# 12_GPS_MIPI_EIM.net
KiCad netlist of a schematic drawn in Altium Designer
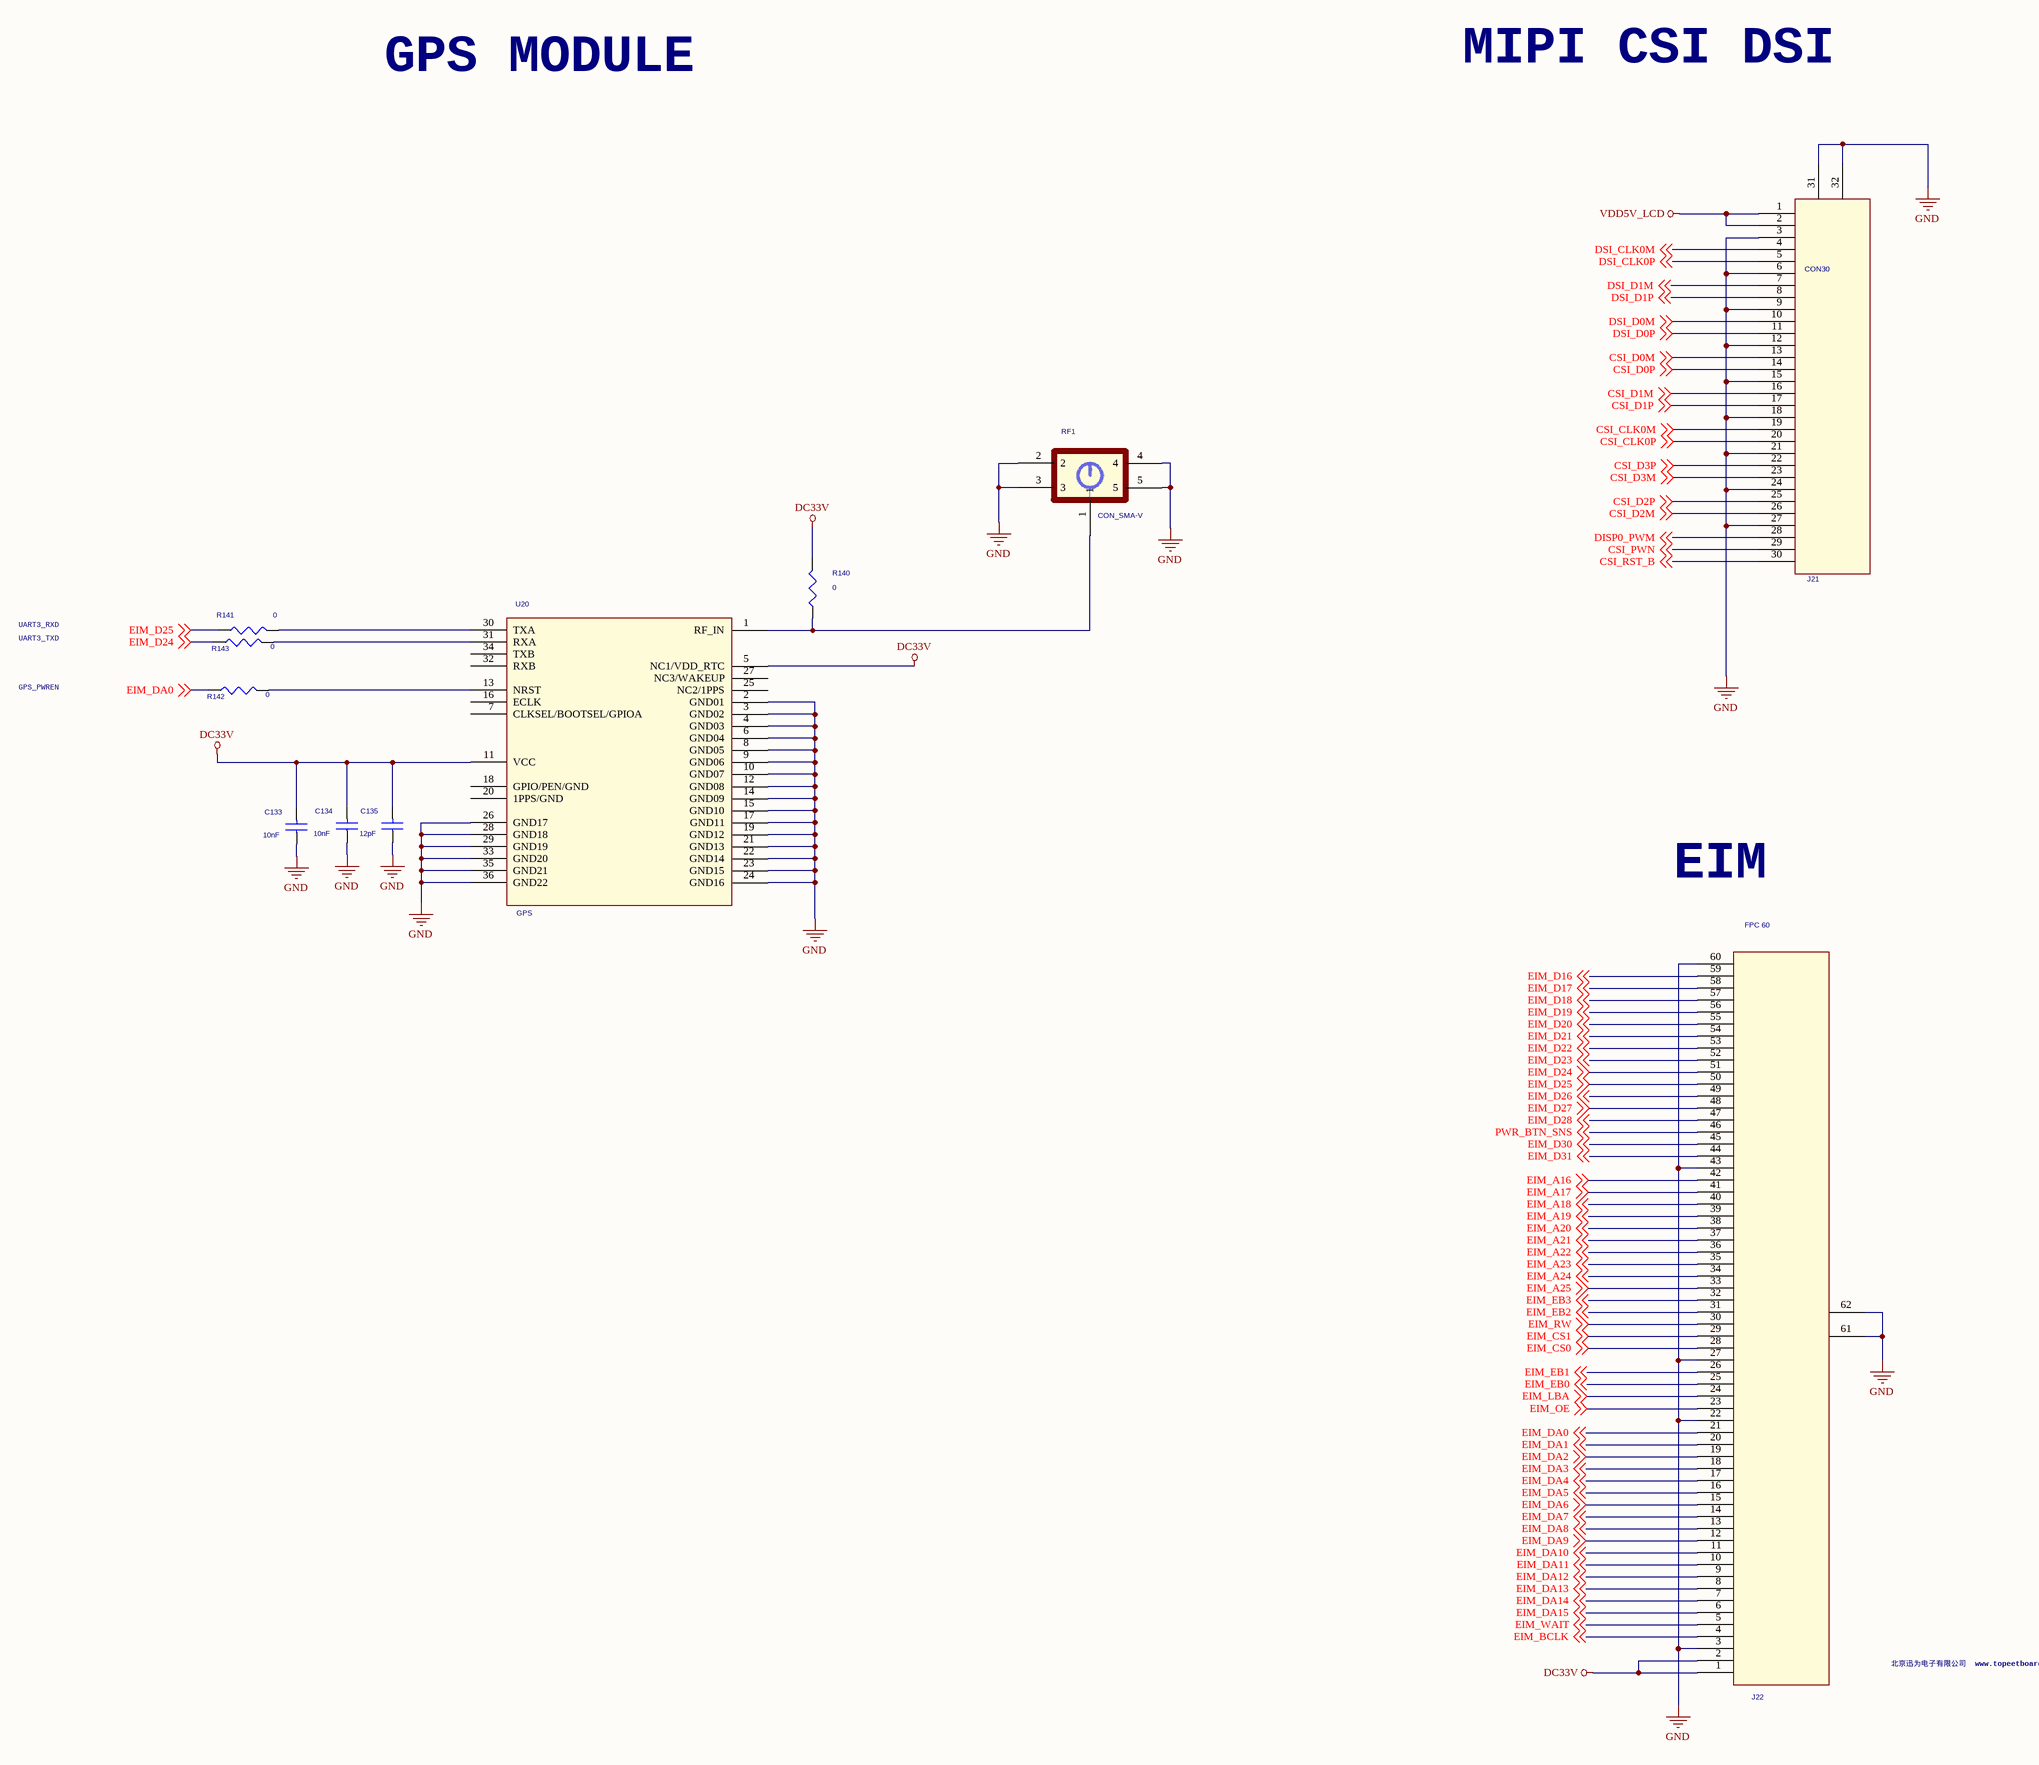
[diagram p0: 12 GPS,MIPI,EIM.SchDoc]

(export (version "E")
  (design (tool "Eeschema 10.0.6"))
  (components
    (comp (ref "C133") (value "10nF") (footprint "C1005") (libsource (lib "*") (part "C1005_Dup1")))
    (comp (ref "C134") (value "10nF") (footprint "C1005") (libsource (lib "*") (part "C1005_Dup1")))
    (comp (ref "C135") (value "12pF") (footprint "C1005") (libsource (lib "*") (part "C1005_Dup1")))
    (comp (ref "J21") (value "CON30") (libsource (lib "*") (part "LVDS_QM_2")))
    (comp (ref "J22") (value "FPC 60") (libsource (lib "*") (part "HEADER 60_1")))
    (comp (ref "R140") (value "0") (footprint "R1005") (libsource (lib "*") (part "R1005_0_Dup1")))
    (comp (ref "R141") (value "0") (footprint "R1005") (libsource (lib "*") (part "R1005_0_Dup1")))
    (comp (ref "R142") (value "0") (footprint "R1005") (libsource (lib "*") (part "R1005_0_Dup1")))
    (comp (ref "R143") (value "0") (footprint "R1005") (libsource (lib "*") (part "R1005_0_Dup1")))
    (comp (ref "RF1") (value "CON_SMA-V") (libsource (lib "*") (part "CON_SMA-V")))
    (comp (ref "U20") (value "GPS") (libsource (lib "*") (part "SM-05")))
  )
  (nets
    (net (code "1") (name "CSI_CLK0M") (class "Default")
      (node (ref "J21") (pin "19") (pinfunction "$PIN11_19") (pintype "passive"))
    )
    (net (code "2") (name "CSI_CLK0P") (class "Default")
      (node (ref "J21") (pin "20") (pinfunction "$PIN10_20") (pintype "passive"))
    )
    (net (code "3") (name "CSI_D0M") (class "Default")
      (node (ref "J21") (pin "13") (pinfunction "$PIN17_13") (pintype "passive"))
    )
    (net (code "4") (name "CSI_D0P") (class "Default")
      (node (ref "J21") (pin "14") (pinfunction "$PIN16_14") (pintype "passive"))
    )
    (net (code "5") (name "CSI_D1M") (class "Default")
      (node (ref "J21") (pin "16") (pinfunction "$PIN14_16") (pintype "passive"))
    )
    (net (code "6") (name "CSI_D1P") (class "Default")
      (node (ref "J21") (pin "17") (pinfunction "$PIN13_17") (pintype "passive"))
    )
    (net (code "7") (name "CSI_D2M") (class "Default")
      (node (ref "J21") (pin "26") (pinfunction "$PIN4_26") (pintype "passive"))
    )
    (net (code "8") (name "CSI_D2P") (class "Default")
      (node (ref "J21") (pin "25") (pinfunction "$PIN5_25") (pintype "passive"))
    )
    (net (code "9") (name "CSI_D3M") (class "Default")
      (node (ref "J21") (pin "23") (pinfunction "$PIN7_23") (pintype "passive"))
    )
    (net (code "10") (name "CSI_D3P") (class "Default")
      (node (ref "J21") (pin "22") (pinfunction "$PIN8_22") (pintype "passive"))
    )
    (net (code "11") (name "CSI_PWN") (class "Default")
      (node (ref "J21") (pin "29") (pinfunction "$PIN1_29") (pintype "passive"))
    )
    (net (code "12") (name "CSI_RST_B") (class "Default")
      (node (ref "J21") (pin "30") (pinfunction "$PIN0_30") (pintype "passive"))
    )
    (net (code "13") (name "DC33V") (class "Default")
      (node (ref "C133") (pin "2") (pinfunction "2_2") (pintype "passive"))
      (node (ref "C134") (pin "2") (pinfunction "2_2") (pintype "passive"))
      (node (ref "C135") (pin "2") (pinfunction "2_2") (pintype "passive"))
      (node (ref "J22") (pin "1") (pinfunction "1_1") (pintype "passive"))
      (node (ref "J22") (pin "2") (pinfunction "2_2") (pintype "passive"))
      (node (ref "R140") (pin "2") (pinfunction "2_2") (pintype "passive"))
      (node (ref "U20") (pin "11") (pinfunction "VCC_11") (pintype "passive"))
      (node (ref "U20") (pin "5") (pinfunction "NC1/VDD_RTC_5") (pintype "passive"))
    )
    (net (code "14") (name "DISP0_PWM") (class "Default")
      (node (ref "J21") (pin "28") (pinfunction "$PIN2_28") (pintype "passive"))
    )
    (net (code "15") (name "DSI_CLK0M") (class "Default")
      (node (ref "J21") (pin "4") (pinfunction "$PIN27_4") (pintype "passive"))
    )
    (net (code "16") (name "DSI_CLK0P") (class "Default")
      (node (ref "J21") (pin "5") (pinfunction "$PIN26_5") (pintype "passive"))
    )
    (net (code "17") (name "DSI_D0M") (class "Default")
      (node (ref "J21") (pin "10") (pinfunction "$PIN20_10") (pintype "passive"))
    )
    (net (code "18") (name "DSI_D0P") (class "Default")
      (node (ref "J21") (pin "11") (pinfunction "$PIN19_11") (pintype "passive"))
    )
    (net (code "19") (name "DSI_D1M") (class "Default")
      (node (ref "J21") (pin "7") (pinfunction "$PIN24_7") (pintype "passive"))
    )
    (net (code "20") (name "DSI_D1P") (class "Default")
      (node (ref "J21") (pin "8") (pinfunction "$PIN22_8") (pintype "passive"))
    )
    (net (code "21") (name "EIM_A16") (class "Default")
      (node (ref "J22") (pin "42") (pinfunction "42_42") (pintype "passive"))
    )
    (net (code "22") (name "EIM_A17") (class "Default")
      (node (ref "J22") (pin "41") (pinfunction "41_41") (pintype "passive"))
    )
    (net (code "23") (name "EIM_A18") (class "Default")
      (node (ref "J22") (pin "40") (pinfunction "40_40") (pintype "passive"))
    )
    (net (code "24") (name "EIM_A19") (class "Default")
      (node (ref "J22") (pin "39") (pinfunction "39_39") (pintype "passive"))
    )
    (net (code "25") (name "EIM_A20") (class "Default")
      (node (ref "J22") (pin "38") (pinfunction "38_38") (pintype "passive"))
    )
    (net (code "26") (name "EIM_A21") (class "Default")
      (node (ref "J22") (pin "37") (pinfunction "37_37") (pintype "passive"))
    )
    (net (code "27") (name "EIM_A22") (class "Default")
      (node (ref "J22") (pin "36") (pinfunction "36_36") (pintype "passive"))
    )
    (net (code "28") (name "EIM_A23") (class "Default")
      (node (ref "J22") (pin "35") (pinfunction "35_35") (pintype "passive"))
    )
    (net (code "29") (name "EIM_A24") (class "Default")
      (node (ref "J22") (pin "34") (pinfunction "34_34") (pintype "passive"))
    )
    (net (code "30") (name "EIM_A25") (class "Default")
      (node (ref "J22") (pin "33") (pinfunction "33_33") (pintype "passive"))
    )
    (net (code "31") (name "EIM_BCLK") (class "Default")
      (node (ref "J22") (pin "4") (pinfunction "4_4") (pintype "passive"))
    )
    (net (code "32") (name "EIM_CS0") (class "Default")
      (node (ref "J22") (pin "28") (pinfunction "28_28") (pintype "passive"))
    )
    (net (code "33") (name "EIM_CS1") (class "Default")
      (node (ref "J22") (pin "29") (pinfunction "29_29") (pintype "passive"))
    )
    (net (code "34") (name "EIM_D16") (class "Default")
      (node (ref "J22") (pin "59") (pinfunction "59_59") (pintype "passive"))
    )
    (net (code "35") (name "EIM_D17") (class "Default")
      (node (ref "J22") (pin "58") (pinfunction "58_58") (pintype "passive"))
    )
    (net (code "36") (name "EIM_D18") (class "Default")
      (node (ref "J22") (pin "57") (pinfunction "57_57") (pintype "passive"))
    )
    (net (code "37") (name "EIM_D19") (class "Default")
      (node (ref "J22") (pin "56") (pinfunction "56_56") (pintype "passive"))
    )
    (net (code "38") (name "EIM_D20") (class "Default")
      (node (ref "J22") (pin "55") (pinfunction "55_55") (pintype "passive"))
    )
    (net (code "39") (name "EIM_D21") (class "Default")
      (node (ref "J22") (pin "54") (pinfunction "54_54") (pintype "passive"))
    )
    (net (code "40") (name "EIM_D22") (class "Default")
      (node (ref "J22") (pin "53") (pinfunction "53_53") (pintype "passive"))
    )
    (net (code "41") (name "EIM_D23") (class "Default")
      (node (ref "J22") (pin "52") (pinfunction "52_52") (pintype "passive"))
    )
    (net (code "42") (name "EIM_D24") (class "Default")
      (node (ref "J22") (pin "51") (pinfunction "51_51") (pintype "passive"))
      (node (ref "R143") (pin "1") (pinfunction "1_1") (pintype "passive"))
    )
    (net (code "43") (name "EIM_D25") (class "Default")
      (node (ref "J22") (pin "50") (pinfunction "50_50") (pintype "passive"))
      (node (ref "R141") (pin "1") (pinfunction "1_1") (pintype "passive"))
    )
    (net (code "44") (name "EIM_D26") (class "Default")
      (node (ref "J22") (pin "49") (pinfunction "49_49") (pintype "passive"))
    )
    (net (code "45") (name "EIM_D27") (class "Default")
      (node (ref "J22") (pin "48") (pinfunction "48_48") (pintype "passive"))
    )
    (net (code "46") (name "EIM_D28") (class "Default")
      (node (ref "J22") (pin "47") (pinfunction "47_47") (pintype "passive"))
    )
    (net (code "47") (name "EIM_D30") (class "Default")
      (node (ref "J22") (pin "45") (pinfunction "45_45") (pintype "passive"))
    )
    (net (code "48") (name "EIM_D31") (class "Default")
      (node (ref "J22") (pin "44") (pinfunction "44_44") (pintype "passive"))
    )
    (net (code "49") (name "EIM_DA0") (class "Default")
      (node (ref "J22") (pin "21") (pinfunction "21_21") (pintype "passive"))
      (node (ref "R142") (pin "1") (pinfunction "1_1") (pintype "passive"))
    )
    (net (code "50") (name "EIM_DA1") (class "Default")
      (node (ref "J22") (pin "20") (pinfunction "20_20") (pintype "passive"))
    )
    (net (code "51") (name "EIM_DA2") (class "Default")
      (node (ref "J22") (pin "19") (pinfunction "19_19") (pintype "passive"))
    )
    (net (code "52") (name "EIM_DA3") (class "Default")
      (node (ref "J22") (pin "18") (pinfunction "18_18") (pintype "passive"))
    )
    (net (code "53") (name "EIM_DA4") (class "Default")
      (node (ref "J22") (pin "17") (pinfunction "17_17") (pintype "passive"))
    )
    (net (code "54") (name "EIM_DA5") (class "Default")
      (node (ref "J22") (pin "16") (pinfunction "16_16") (pintype "passive"))
    )
    (net (code "55") (name "EIM_DA6") (class "Default")
      (node (ref "J22") (pin "15") (pinfunction "15_15") (pintype "passive"))
    )
    (net (code "56") (name "EIM_DA7") (class "Default")
      (node (ref "J22") (pin "14") (pinfunction "14_14") (pintype "passive"))
    )
    (net (code "57") (name "EIM_DA8") (class "Default")
      (node (ref "J22") (pin "13") (pinfunction "13_13") (pintype "passive"))
    )
    (net (code "58") (name "EIM_DA9") (class "Default")
      (node (ref "J22") (pin "12") (pinfunction "12_12") (pintype "passive"))
    )
    (net (code "59") (name "EIM_DA10") (class "Default")
      (node (ref "J22") (pin "11") (pinfunction "11_11") (pintype "passive"))
    )
    (net (code "60") (name "EIM_DA11") (class "Default")
      (node (ref "J22") (pin "10") (pinfunction "10_10") (pintype "passive"))
    )
    (net (code "61") (name "EIM_DA12") (class "Default")
      (node (ref "J22") (pin "9") (pinfunction "9_9") (pintype "passive"))
    )
    (net (code "62") (name "EIM_DA13") (class "Default")
      (node (ref "J22") (pin "8") (pinfunction "8_8") (pintype "passive"))
    )
    (net (code "63") (name "EIM_DA14") (class "Default")
      (node (ref "J22") (pin "7") (pinfunction "7_7") (pintype "passive"))
    )
    (net (code "64") (name "EIM_DA15") (class "Default")
      (node (ref "J22") (pin "6") (pinfunction "6_6") (pintype "passive"))
    )
    (net (code "65") (name "EIM_EB0") (class "Default")
      (node (ref "J22") (pin "25") (pinfunction "25_25") (pintype "passive"))
    )
    (net (code "66") (name "EIM_EB1") (class "Default")
      (node (ref "J22") (pin "26") (pinfunction "26_26") (pintype "passive"))
    )
    (net (code "67") (name "EIM_EB2") (class "Default")
      (node (ref "J22") (pin "31") (pinfunction "31_31") (pintype "passive"))
    )
    (net (code "68") (name "EIM_EB3") (class "Default")
      (node (ref "J22") (pin "32") (pinfunction "32_32") (pintype "passive"))
    )
    (net (code "69") (name "EIM_LBA") (class "Default")
      (node (ref "J22") (pin "24") (pinfunction "24_24") (pintype "passive"))
    )
    (net (code "70") (name "EIM_OE") (class "Default")
      (node (ref "J22") (pin "23") (pinfunction "23_23") (pintype "passive"))
    )
    (net (code "71") (name "EIM_RW") (class "Default")
      (node (ref "J22") (pin "30") (pinfunction "30_30") (pintype "passive"))
    )
    (net (code "72") (name "EIM_WAIT") (class "Default")
      (node (ref "J22") (pin "5") (pinfunction "5_5") (pintype "passive"))
    )
    (net (code "73") (name "GND") (class "Default")
      (node (ref "C133") (pin "1") (pinfunction "1_1") (pintype "passive"))
      (node (ref "C134") (pin "1") (pinfunction "1_1") (pintype "passive"))
      (node (ref "C135") (pin "1") (pinfunction "1_1") (pintype "passive"))
      (node (ref "J21") (pin "12") (pinfunction "$PIN18_12") (pintype "passive"))
      (node (ref "J21") (pin "15") (pinfunction "$PIN15_15") (pintype "passive"))
      (node (ref "J21") (pin "18") (pinfunction "$PIN12_18") (pintype "passive"))
      (node (ref "J21") (pin "21") (pinfunction "$PIN9_21") (pintype "passive"))
      (node (ref "J21") (pin "24") (pinfunction "$PIN6_24") (pintype "passive"))
      (node (ref "J21") (pin "27") (pinfunction "$PIN3_27") (pintype "passive"))
      (node (ref "J21") (pin "3") (pinfunction "$PIN28_3") (pintype "passive"))
      (node (ref "J21") (pin "31") (pinfunction "31_31") (pintype "passive"))
      (node (ref "J21") (pin "32") (pinfunction "32_32") (pintype "passive"))
      (node (ref "J21") (pin "6") (pinfunction "$PIN25_6") (pintype "passive"))
      (node (ref "J21") (pin "9") (pinfunction "$PIN21_9") (pintype "passive"))
      (node (ref "J22") (pin "22") (pinfunction "22_22") (pintype "passive"))
      (node (ref "J22") (pin "27") (pinfunction "27_27") (pintype "passive"))
      (node (ref "J22") (pin "3") (pinfunction "3_3") (pintype "passive"))
      (node (ref "J22") (pin "43") (pinfunction "43_43") (pintype "passive"))
      (node (ref "J22") (pin "60") (pinfunction "60_60") (pintype "passive"))
      (node (ref "J22") (pin "61") (pinfunction "61_61") (pintype "passive"))
      (node (ref "J22") (pin "62") (pinfunction "62_62") (pintype "passive"))
      (node (ref "RF1") (pin "2") (pinfunction "2_2") (pintype "passive"))
      (node (ref "RF1") (pin "3") (pinfunction "3_3") (pintype "passive"))
      (node (ref "RF1") (pin "4") (pinfunction "4_4") (pintype "passive"))
      (node (ref "RF1") (pin "5") (pinfunction "5_5") (pintype "passive"))
      (node (ref "U20") (pin "10") (pinfunction "GND07_10") (pintype "passive"))
      (node (ref "U20") (pin "12") (pinfunction "GND08_12") (pintype "passive"))
      (node (ref "U20") (pin "14") (pinfunction "GND09_14") (pintype "passive"))
      (node (ref "U20") (pin "15") (pinfunction "GND10_15") (pintype "passive"))
      (node (ref "U20") (pin "17") (pinfunction "GND11_17") (pintype "passive"))
      (node (ref "U20") (pin "19") (pinfunction "GND12_19") (pintype "passive"))
      (node (ref "U20") (pin "2") (pinfunction "GND01_2") (pintype "passive"))
      (node (ref "U20") (pin "21") (pinfunction "GND13_21") (pintype "passive"))
      (node (ref "U20") (pin "22") (pinfunction "GND14_22") (pintype "passive"))
      (node (ref "U20") (pin "23") (pinfunction "GND15_23") (pintype "passive"))
      (node (ref "U20") (pin "24") (pinfunction "GND16_24") (pintype "passive"))
      (node (ref "U20") (pin "26") (pinfunction "GND17_26") (pintype "passive"))
      (node (ref "U20") (pin "28") (pinfunction "GND18_28") (pintype "passive"))
      (node (ref "U20") (pin "29") (pinfunction "GND19_29") (pintype "passive"))
      (node (ref "U20") (pin "3") (pinfunction "GND02_3") (pintype "passive"))
      (node (ref "U20") (pin "33") (pinfunction "GND20_33") (pintype "passive"))
      (node (ref "U20") (pin "35") (pinfunction "GND21_35") (pintype "passive"))
      (node (ref "U20") (pin "36") (pinfunction "GND22_36") (pintype "passive"))
      (node (ref "U20") (pin "4") (pinfunction "GND03_4") (pintype "passive"))
      (node (ref "U20") (pin "6") (pinfunction "GND04_6") (pintype "passive"))
      (node (ref "U20") (pin "8") (pinfunction "GND05_8") (pintype "passive"))
      (node (ref "U20") (pin "9") (pinfunction "GND06_9") (pintype "passive"))
    )
    (net (code "74") (name "Net-(U20-NRST)") (class "Default")
      (node (ref "R142") (pin "2") (pinfunction "2_2") (pintype "passive"))
      (node (ref "U20") (pin "13") (pinfunction "NRST_13") (pintype "passive"))
    )
    (net (code "75") (name "Net-(U20-RF_IN)") (class "Default")
      (node (ref "R140") (pin "1") (pinfunction "1_1") (pintype "passive"))
      (node (ref "RF1") (pin "1") (pinfunction "1_1") (pintype "passive"))
      (node (ref "U20") (pin "1") (pinfunction "RF_IN_1") (pintype "passive"))
    )
    (net (code "76") (name "Net-(U20-RXA)") (class "Default")
      (node (ref "R143") (pin "2") (pinfunction "2_2") (pintype "passive"))
      (node (ref "U20") (pin "31") (pinfunction "RXA_31") (pintype "passive"))
    )
    (net (code "77") (name "Net-(U20-TXA)") (class "Default")
      (node (ref "R141") (pin "2") (pinfunction "2_2") (pintype "passive"))
      (node (ref "U20") (pin "30") (pinfunction "TXA_30") (pintype "passive"))
    )
    (net (code "78") (name "PWR_BTN_SNS") (class "Default")
      (node (ref "J22") (pin "46") (pinfunction "46_46") (pintype "passive"))
    )
    (net (code "79") (name "VDD5V_LCD") (class "Default")
      (node (ref "J21") (pin "1") (pinfunction "$PIN30_1") (pintype "passive"))
      (node (ref "J21") (pin "2") (pinfunction "$PIN29_2") (pintype "passive"))
    )
    (net (code "80") (name "unconnected-(U20-1PPS{slash}GND-Pad20)") (class "Default")
      (node (ref "U20") (pin "20") (pinfunction "1PPS/GND_20") (pintype "passive"))
    )
    (net (code "81") (name "unconnected-(U20-CLKSEL{slash}BOOTSEL{slash}GPIOA-Pad7)") (class "Default")
      (node (ref "U20") (pin "7") (pinfunction "CLKSEL/BOOTSEL/GPIOA_7") (pintype "passive"))
    )
    (net (code "82") (name "unconnected-(U20-ECLK-Pad16)") (class "Default")
      (node (ref "U20") (pin "16") (pinfunction "ECLK_16") (pintype "passive"))
    )
    (net (code "83") (name "unconnected-(U20-GPIO{slash}PEN{slash}GND-Pad18)") (class "Default")
      (node (ref "U20") (pin "18") (pinfunction "GPIO/PEN/GND_18") (pintype "passive"))
    )
    (net (code "84") (name "unconnected-(U20-NC2{slash}1PPS-Pad25)") (class "Default")
      (node (ref "U20") (pin "25") (pinfunction "NC2/1PPS_25") (pintype "passive"))
    )
    (net (code "85") (name "unconnected-(U20-NC3{slash}WAKEUP-Pad27)") (class "Default")
      (node (ref "U20") (pin "27") (pinfunction "NC3/WAKEUP_27") (pintype "passive"))
    )
    (net (code "86") (name "unconnected-(U20-RXB-Pad32)") (class "Default")
      (node (ref "U20") (pin "32") (pinfunction "RXB_32") (pintype "passive"))
    )
    (net (code "87") (name "unconnected-(U20-TXB-Pad34)") (class "Default")
      (node (ref "U20") (pin "34") (pinfunction "TXB_34") (pintype "passive"))
    )
  )
)
